# Keyglove_Kit_v0_4.net
KiCad netlist of a schematic drawn in EAGLE
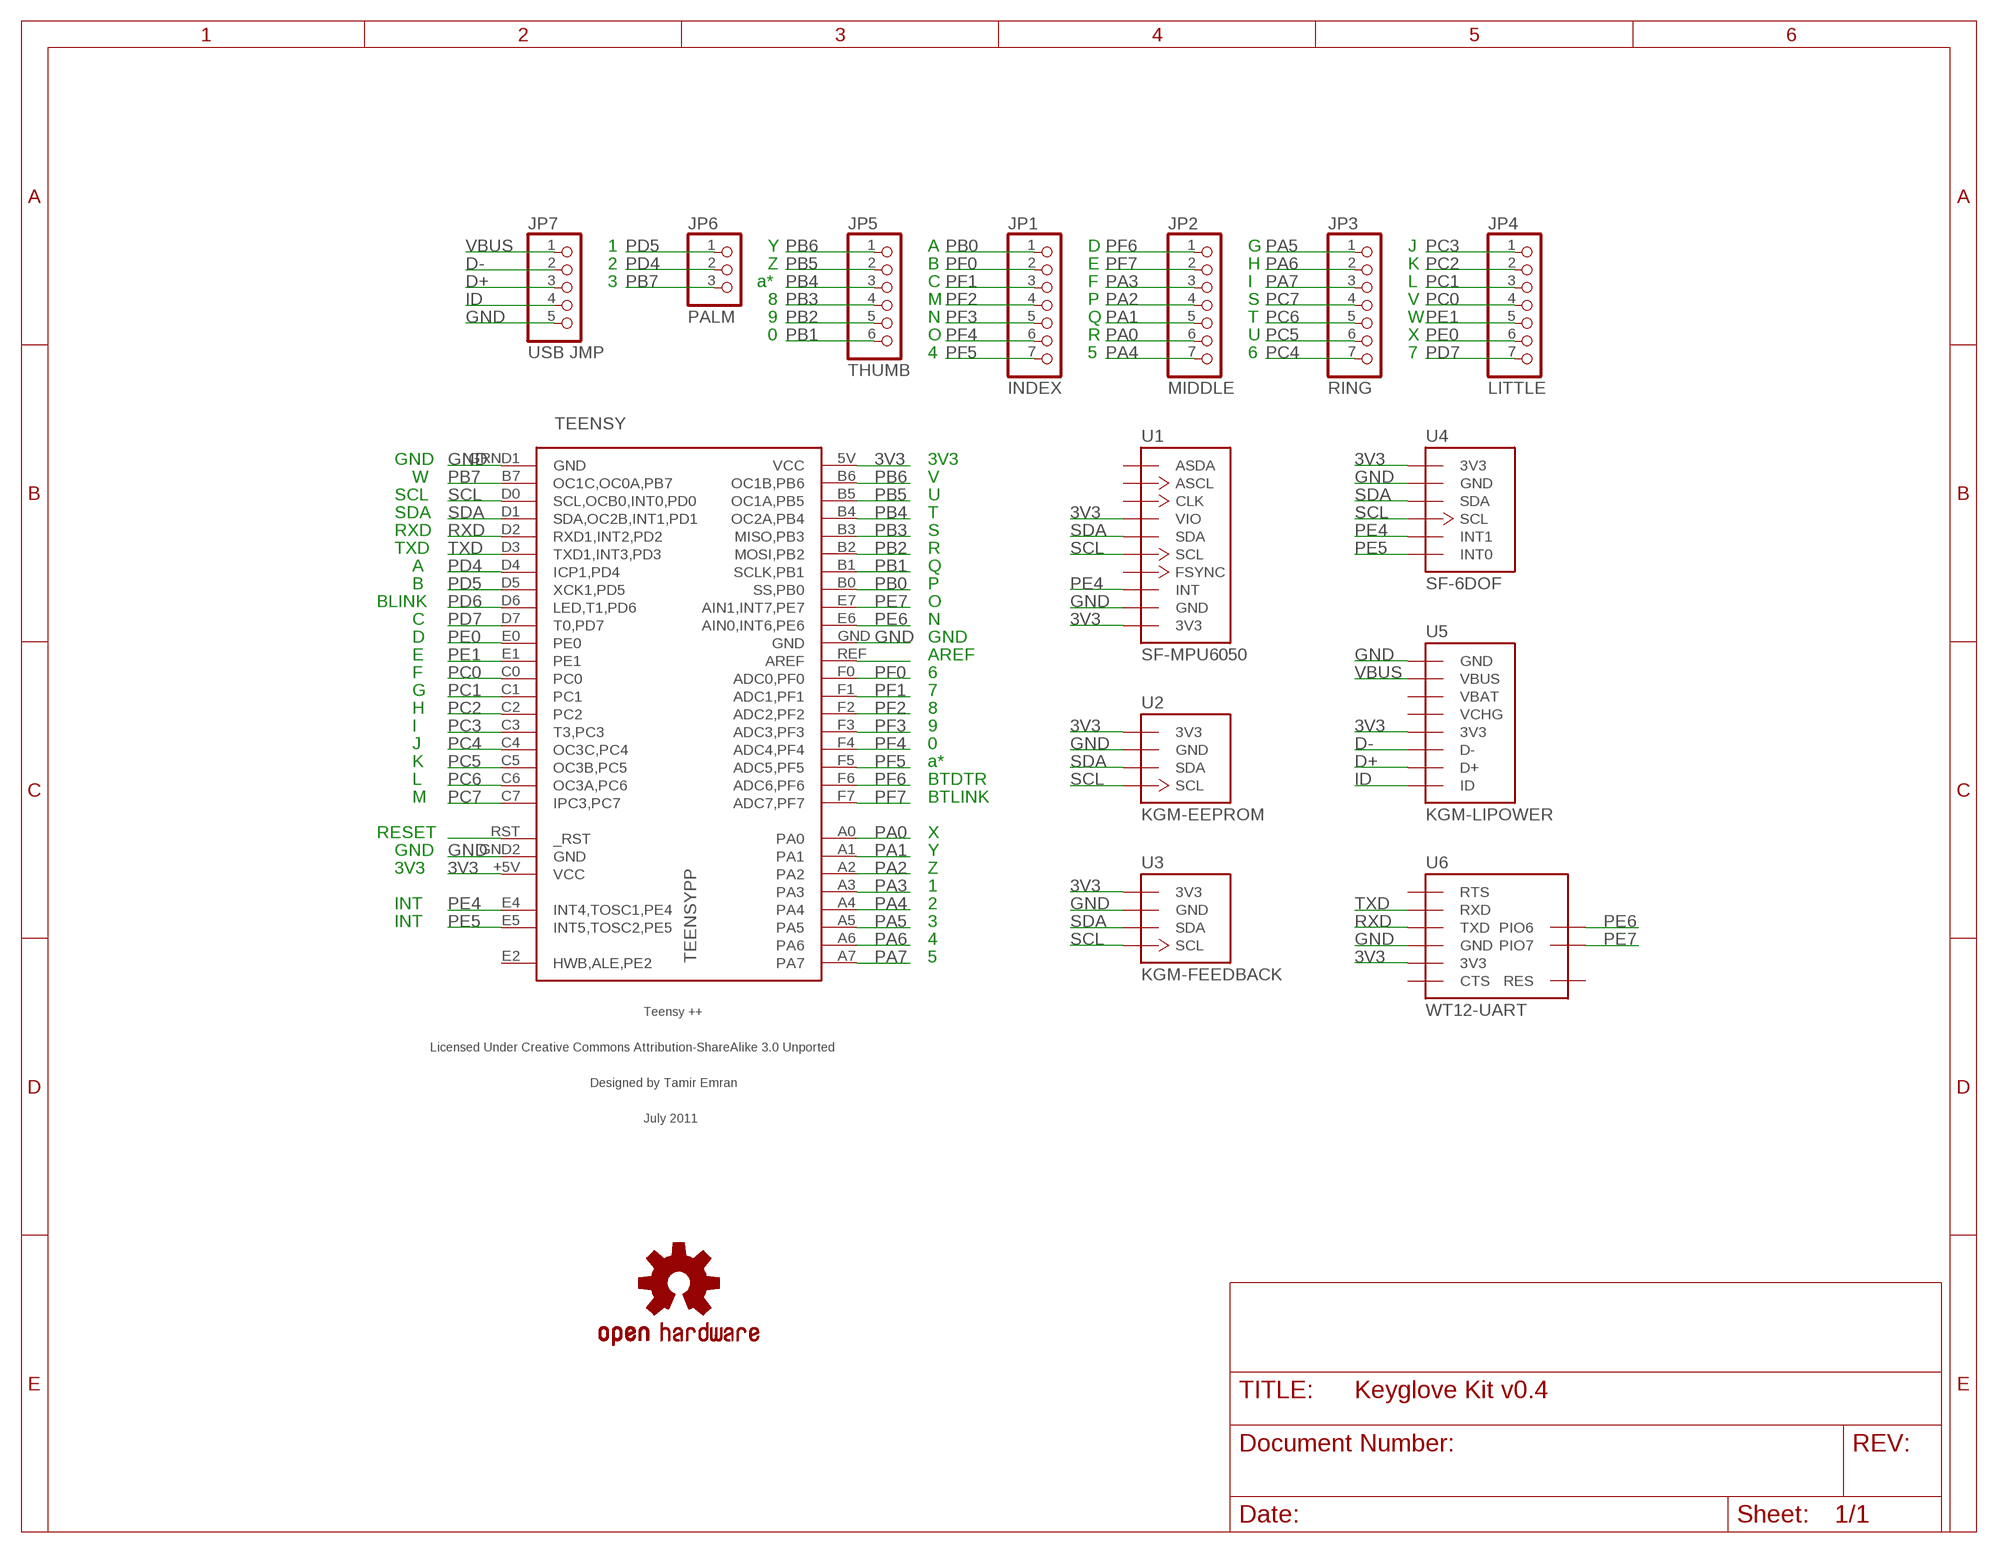
[diagram p0: schematic, sheet 1]

(export (version "E")
  (design (tool "Eeschema 10.0.6"))
  (components
    (comp (ref "JP1")
      (value "INDEX")
      (footprint "eagle-import:1X07")
      (libsource (lib "eagle-import") (part "PINHD-1X7"))
    )
    (comp (ref "JP2")
      (value "MIDDLE")
      (footprint "eagle-import:1X07")
      (libsource (lib "eagle-import") (part "PINHD-1X7"))
    )
    (comp (ref "JP3")
      (value "RING")
      (footprint "eagle-import:1X07")
      (libsource (lib "eagle-import") (part "PINHD-1X7"))
    )
    (comp (ref "JP4")
      (value "LITTLE")
      (footprint "eagle-import:1X07")
      (libsource (lib "eagle-import") (part "PINHD-1X7"))
    )
    (comp (ref "JP5")
      (value "THUMB")
      (footprint "eagle-import:1X06")
      (libsource (lib "eagle-import") (part "PINHD-1X6"))
    )
    (comp (ref "JP6")
      (value "PALM")
      (footprint "eagle-import:1X03")
      (libsource (lib "eagle-import") (part "PINHD-1X3"))
    )
    (comp (ref "JP7")
      (value "USB JMP")
      (footprint "eagle-import:1X05")
      (libsource (lib "eagle-import") (part "PINHD-1X5"))
    )
    (comp (ref "TEENSY")
      (value "TEENSYPP")
      (footprint "eagle-import:TEENSYPP")
      (libsource (lib "eagle-import") (part "TEENSYPP"))
    )
    (comp (ref "U$1")
      (value "OSHW-LOGOM")
      (footprint "eagle-import:OSHW-LOGO-M")
      (libsource (lib "eagle-import") (part "OSHW-LOGOM"))
    )
    (comp (ref "U1")
      (value "SF-MPU6050")
      (footprint "eagle-import:SF-MPU6050")
      (libsource (lib "eagle-import") (part "SF-MPU6050"))
    )
    (comp (ref "U2")
      (value "KGM-EEPROM")
      (footprint "eagle-import:KGM-EEPROM")
      (libsource (lib "eagle-import") (part "KGM-EEPROM"))
    )
    (comp (ref "U3")
      (value "KGM-FEEDBACK")
      (footprint "eagle-import:KGM-FEEDBACK")
      (libsource (lib "eagle-import") (part "KGM-FEEDBACK"))
    )
    (comp (ref "U4")
      (value "SF-6DOF")
      (footprint "eagle-import:SF-6DOF")
      (libsource (lib "eagle-import") (part "SF-6DOF"))
    )
    (comp (ref "U5")
      (value "KGM-LIPOWER")
      (footprint "eagle-import:KGM-LIPOWER")
      (libsource (lib "eagle-import") (part "KGM-LIPOWER"))
    )
    (comp (ref "U6")
      (value "WT12-UART")
      (footprint "eagle-import:WT12-UART")
      (libsource (lib "eagle-import") (part "WT12-UART"))
    )
  )
  (nets
    (net (code "1") (name "/3V3") (class "Default")
      (node (ref "TEENSY") (pin "+5V") (pinfunction "VCC_+5V") (pintype "power_in"))
      (node (ref "TEENSY") (pin "5V") (pinfunction "VCC_5V") (pintype "power_in"))
      (node (ref "U1") (pin "3V3") (pinfunction "3V3_3V3") (pintype "power_in"))
      (node (ref "U1") (pin "VIO") (pinfunction "VIO_VIO") (pintype "power_in"))
      (node (ref "U2") (pin "3V3") (pinfunction "3V3_3V3") (pintype "power_in"))
      (node (ref "U3") (pin "3V3") (pinfunction "3V3_3V3") (pintype "power_in"))
      (node (ref "U4") (pin "3V3") (pinfunction "3V3_3V3") (pintype "power_in"))
      (node (ref "U5") (pin "3V3") (pinfunction "3V3_3V3") (pintype "power_in"))
      (node (ref "U6") (pin "3V3") (pinfunction "3V3_3V3") (pintype "power_in"))
    )
    (net (code "2") (name "/D+") (class "Default")
      (node (ref "JP7") (pin "3") (pinfunction "3_3") (pintype "passive"))
      (node (ref "U5") (pin "D+") (pinfunction "D+_D+") (pintype "bidirectional"))
    )
    (net (code "3") (name "/D-") (class "Default")
      (node (ref "JP7") (pin "2") (pinfunction "2_2") (pintype "passive"))
      (node (ref "U5") (pin "D-") (pinfunction "D-_D-") (pintype "bidirectional"))
    )
    (net (code "4") (name "/GND") (class "Default")
      (node (ref "JP7") (pin "5") (pinfunction "5_5") (pintype "passive"))
      (node (ref "TEENSY") (pin "GND") (pinfunction "GND_GND") (pintype "power_in"))
      (node (ref "TEENSY") (pin "GND2") (pinfunction "GND_GND2") (pintype "power_in"))
      (node (ref "TEENSY") (pin "GRND1") (pinfunction "GND_GRND1") (pintype "power_in"))
      (node (ref "U1") (pin "GND") (pinfunction "GND_GND") (pintype "power_in"))
      (node (ref "U2") (pin "GND") (pinfunction "GND_GND") (pintype "power_in"))
      (node (ref "U3") (pin "GND") (pinfunction "GND_GND") (pintype "power_in"))
      (node (ref "U4") (pin "GND") (pinfunction "GND_GND") (pintype "power_in"))
      (node (ref "U5") (pin "GND") (pinfunction "GND_GND") (pintype "power_in"))
      (node (ref "U6") (pin "GND") (pinfunction "GND_GND") (pintype "power_in"))
    )
    (net (code "5") (name "/ID") (class "Default")
      (node (ref "JP7") (pin "4") (pinfunction "4_4") (pintype "passive"))
      (node (ref "U5") (pin "ID") (pinfunction "ID_ID") (pintype "bidirectional"))
    )
    (net (code "6") (name "/PA0") (class "Default")
      (node (ref "JP2") (pin "6") (pinfunction "6_6") (pintype "passive"))
      (node (ref "TEENSY") (pin "A0") (pinfunction "PA0_A0") (pintype "bidirectional"))
    )
    (net (code "7") (name "/PA1") (class "Default")
      (node (ref "JP2") (pin "5") (pinfunction "5_5") (pintype "passive"))
      (node (ref "TEENSY") (pin "A1") (pinfunction "PA1_A1") (pintype "bidirectional"))
    )
    (net (code "8") (name "/PA2") (class "Default")
      (node (ref "JP2") (pin "4") (pinfunction "4_4") (pintype "passive"))
      (node (ref "TEENSY") (pin "A2") (pinfunction "PA2_A2") (pintype "bidirectional"))
    )
    (net (code "9") (name "/PA3") (class "Default")
      (node (ref "JP2") (pin "3") (pinfunction "3_3") (pintype "passive"))
      (node (ref "TEENSY") (pin "A3") (pinfunction "PA3_A3") (pintype "bidirectional"))
    )
    (net (code "10") (name "/PA4") (class "Default")
      (node (ref "JP2") (pin "7") (pinfunction "7_7") (pintype "passive"))
      (node (ref "TEENSY") (pin "A4") (pinfunction "PA4_A4") (pintype "bidirectional"))
    )
    (net (code "11") (name "/PA5") (class "Default")
      (node (ref "JP3") (pin "1") (pinfunction "1_1") (pintype "passive"))
      (node (ref "TEENSY") (pin "A5") (pinfunction "PA5_A5") (pintype "bidirectional"))
    )
    (net (code "12") (name "/PA6") (class "Default")
      (node (ref "JP3") (pin "2") (pinfunction "2_2") (pintype "passive"))
      (node (ref "TEENSY") (pin "A6") (pinfunction "PA6_A6") (pintype "bidirectional"))
    )
    (net (code "13") (name "/PA7") (class "Default")
      (node (ref "JP3") (pin "3") (pinfunction "3_3") (pintype "passive"))
      (node (ref "TEENSY") (pin "A7") (pinfunction "PA7_A7") (pintype "bidirectional"))
    )
    (net (code "14") (name "/PB0") (class "Default")
      (node (ref "JP1") (pin "1") (pinfunction "1_1") (pintype "passive"))
      (node (ref "TEENSY") (pin "B0") (pinfunction "SS,PB0_B0") (pintype "bidirectional"))
    )
    (net (code "15") (name "/PB1") (class "Default")
      (node (ref "JP5") (pin "6") (pinfunction "6_6") (pintype "passive"))
      (node (ref "TEENSY") (pin "B1") (pinfunction "SCLK,PB1_B1") (pintype "bidirectional"))
    )
    (net (code "16") (name "/PB2") (class "Default")
      (node (ref "JP5") (pin "5") (pinfunction "5_5") (pintype "passive"))
      (node (ref "TEENSY") (pin "B2") (pinfunction "MOSI,PB2_B2") (pintype "bidirectional"))
    )
    (net (code "17") (name "/PB3") (class "Default")
      (node (ref "JP5") (pin "4") (pinfunction "4_4") (pintype "passive"))
      (node (ref "TEENSY") (pin "B3") (pinfunction "MISO,PB3_B3") (pintype "bidirectional"))
    )
    (net (code "18") (name "/PB4") (class "Default")
      (node (ref "JP5") (pin "3") (pinfunction "3_3") (pintype "passive"))
      (node (ref "TEENSY") (pin "B4") (pinfunction "OC2A,PB4_B4") (pintype "bidirectional"))
    )
    (net (code "19") (name "/PB5") (class "Default")
      (node (ref "JP5") (pin "2") (pinfunction "2_2") (pintype "passive"))
      (node (ref "TEENSY") (pin "B5") (pinfunction "OC1A,PB5_B5") (pintype "bidirectional"))
    )
    (net (code "20") (name "/PB6") (class "Default")
      (node (ref "JP5") (pin "1") (pinfunction "1_1") (pintype "passive"))
      (node (ref "TEENSY") (pin "B6") (pinfunction "OC1B,PB6_B6") (pintype "bidirectional"))
    )
    (net (code "21") (name "/PB7") (class "Default")
      (node (ref "JP6") (pin "3") (pinfunction "3_3") (pintype "passive"))
      (node (ref "TEENSY") (pin "B7") (pinfunction "OC1C,OC0A,PB7_B7") (pintype "bidirectional"))
    )
    (net (code "22") (name "/PC0") (class "Default")
      (node (ref "JP4") (pin "4") (pinfunction "4_4") (pintype "passive"))
      (node (ref "TEENSY") (pin "C0") (pinfunction "PC0_C0") (pintype "bidirectional"))
    )
    (net (code "23") (name "/PC1") (class "Default")
      (node (ref "JP4") (pin "3") (pinfunction "3_3") (pintype "passive"))
      (node (ref "TEENSY") (pin "C1") (pinfunction "PC1_C1") (pintype "bidirectional"))
    )
    (net (code "24") (name "/PC2") (class "Default")
      (node (ref "JP4") (pin "2") (pinfunction "2_2") (pintype "passive"))
      (node (ref "TEENSY") (pin "C2") (pinfunction "PC2_C2") (pintype "bidirectional"))
    )
    (net (code "25") (name "/PC3") (class "Default")
      (node (ref "JP4") (pin "1") (pinfunction "1_1") (pintype "passive"))
      (node (ref "TEENSY") (pin "C3") (pinfunction "T3,PC3_C3") (pintype "bidirectional"))
    )
    (net (code "26") (name "/PC4") (class "Default")
      (node (ref "JP3") (pin "7") (pinfunction "7_7") (pintype "passive"))
      (node (ref "TEENSY") (pin "C4") (pinfunction "OC3C,PC4_C4") (pintype "bidirectional"))
    )
    (net (code "27") (name "/PC5") (class "Default")
      (node (ref "JP3") (pin "6") (pinfunction "6_6") (pintype "passive"))
      (node (ref "TEENSY") (pin "C5") (pinfunction "OC3B,PC5_C5") (pintype "bidirectional"))
    )
    (net (code "28") (name "/PC6") (class "Default")
      (node (ref "JP3") (pin "5") (pinfunction "5_5") (pintype "passive"))
      (node (ref "TEENSY") (pin "C6") (pinfunction "OC3A,PC6_C6") (pintype "bidirectional"))
    )
    (net (code "29") (name "/PC7") (class "Default")
      (node (ref "JP3") (pin "4") (pinfunction "4_4") (pintype "passive"))
      (node (ref "TEENSY") (pin "C7") (pinfunction "IPC3,PC7_C7") (pintype "bidirectional"))
    )
    (net (code "30") (name "/PD4") (class "Default")
      (node (ref "JP6") (pin "2") (pinfunction "2_2") (pintype "passive"))
      (node (ref "TEENSY") (pin "D4") (pinfunction "ICP1,PD4_D4") (pintype "bidirectional"))
    )
    (net (code "31") (name "/PD5") (class "Default")
      (node (ref "JP6") (pin "1") (pinfunction "1_1") (pintype "passive"))
      (node (ref "TEENSY") (pin "D5") (pinfunction "XCK1,PD5_D5") (pintype "bidirectional"))
    )
    (net (code "32") (name "/PD6") (class "Default")
      (node (ref "TEENSY") (pin "D6") (pinfunction "LED,T1,PD6_D6") (pintype "bidirectional"))
    )
    (net (code "33") (name "/PD7") (class "Default")
      (node (ref "JP4") (pin "7") (pinfunction "7_7") (pintype "passive"))
      (node (ref "TEENSY") (pin "D7") (pinfunction "T0,PD7_D7") (pintype "bidirectional"))
    )
    (net (code "34") (name "/PE0") (class "Default")
      (node (ref "JP4") (pin "6") (pinfunction "6_6") (pintype "passive"))
      (node (ref "TEENSY") (pin "E0") (pinfunction "PE0_E0") (pintype "bidirectional"))
    )
    (net (code "35") (name "/PE1") (class "Default")
      (node (ref "JP4") (pin "5") (pinfunction "5_5") (pintype "passive"))
      (node (ref "TEENSY") (pin "E1") (pinfunction "PE1_E1") (pintype "bidirectional"))
    )
    (net (code "36") (name "/PE4") (class "Default")
      (node (ref "TEENSY") (pin "E4") (pinfunction "INT4,TOSC1,PE4_E4") (pintype "bidirectional"))
      (node (ref "U1") (pin "INT") (pinfunction "INT_INT") (pintype "output"))
      (node (ref "U4") (pin "INT1") (pinfunction "INT1_INT1") (pintype "output"))
    )
    (net (code "37") (name "/PE5") (class "Default")
      (node (ref "TEENSY") (pin "E5") (pinfunction "INT5,TOSC2,PE5_E5") (pintype "bidirectional"))
      (node (ref "U4") (pin "INT0") (pinfunction "INT0_INT0") (pintype "output"))
    )
    (net (code "38") (name "/PE6") (class "Default")
      (node (ref "TEENSY") (pin "E6") (pinfunction "AIN0,INT6,PE6_E6") (pintype "bidirectional"))
      (node (ref "U6") (pin "PIO6") (pinfunction "PIO6_PIO6") (pintype "bidirectional"))
    )
    (net (code "39") (name "/PE7") (class "Default")
      (node (ref "TEENSY") (pin "E7") (pinfunction "AIN1,INT7,PE7_E7") (pintype "bidirectional"))
      (node (ref "U6") (pin "PIO7") (pinfunction "PIO7_PIO7") (pintype "bidirectional"))
    )
    (net (code "40") (name "/PF0") (class "Default")
      (node (ref "JP1") (pin "2") (pinfunction "2_2") (pintype "passive"))
      (node (ref "TEENSY") (pin "F0") (pinfunction "ADC0,PF0_F0") (pintype "bidirectional"))
    )
    (net (code "41") (name "/PF1") (class "Default")
      (node (ref "JP1") (pin "3") (pinfunction "3_3") (pintype "passive"))
      (node (ref "TEENSY") (pin "F1") (pinfunction "ADC1,PF1_F1") (pintype "bidirectional"))
    )
    (net (code "42") (name "/PF2") (class "Default")
      (node (ref "JP1") (pin "4") (pinfunction "4_4") (pintype "passive"))
      (node (ref "TEENSY") (pin "F2") (pinfunction "ADC2,PF2_F2") (pintype "bidirectional"))
    )
    (net (code "43") (name "/PF3") (class "Default")
      (node (ref "JP1") (pin "5") (pinfunction "5_5") (pintype "passive"))
      (node (ref "TEENSY") (pin "F3") (pinfunction "ADC3,PF3_F3") (pintype "bidirectional"))
    )
    (net (code "44") (name "/PF4") (class "Default")
      (node (ref "JP1") (pin "6") (pinfunction "6_6") (pintype "passive"))
      (node (ref "TEENSY") (pin "F4") (pinfunction "ADC4,PF4_F4") (pintype "bidirectional"))
    )
    (net (code "45") (name "/PF5") (class "Default")
      (node (ref "JP1") (pin "7") (pinfunction "7_7") (pintype "passive"))
      (node (ref "TEENSY") (pin "F5") (pinfunction "ADC5,PF5_F5") (pintype "bidirectional"))
    )
    (net (code "46") (name "/PF6") (class "Default")
      (node (ref "JP2") (pin "1") (pinfunction "1_1") (pintype "passive"))
      (node (ref "TEENSY") (pin "F6") (pinfunction "ADC6,PF6_F6") (pintype "bidirectional"))
    )
    (net (code "47") (name "/PF7") (class "Default")
      (node (ref "JP2") (pin "2") (pinfunction "2_2") (pintype "passive"))
      (node (ref "TEENSY") (pin "F7") (pinfunction "ADC7,PF7_F7") (pintype "bidirectional"))
    )
    (net (code "48") (name "/RXD") (class "Default")
      (node (ref "TEENSY") (pin "D2") (pinfunction "RXD1,INT2,PD2_D2") (pintype "bidirectional"))
      (node (ref "U6") (pin "TXD") (pinfunction "TXD_TXD") (pintype "output"))
    )
    (net (code "49") (name "/SCL") (class "Default")
      (node (ref "TEENSY") (pin "D0") (pinfunction "SCL,OCB0,INT0,PD0_D0") (pintype "bidirectional"))
      (node (ref "U1") (pin "SCL") (pinfunction "SCL_SCL") (pintype "bidirectional"))
      (node (ref "U2") (pin "SCL") (pinfunction "SCL_SCL") (pintype "bidirectional"))
      (node (ref "U3") (pin "SCL") (pinfunction "SCL_SCL") (pintype "bidirectional"))
      (node (ref "U4") (pin "SCL") (pinfunction "SCL_SCL") (pintype "bidirectional"))
    )
    (net (code "50") (name "/SDA") (class "Default")
      (node (ref "TEENSY") (pin "D1") (pinfunction "SDA,OC2B,INT1,PD1_D1") (pintype "bidirectional"))
      (node (ref "U1") (pin "SDA") (pinfunction "SDA_SDA") (pintype "bidirectional"))
      (node (ref "U2") (pin "SDA") (pinfunction "SDA_SDA") (pintype "bidirectional"))
      (node (ref "U3") (pin "SDA") (pinfunction "SDA_SDA") (pintype "bidirectional"))
      (node (ref "U4") (pin "SDA") (pinfunction "SDA_SDA") (pintype "bidirectional"))
    )
    (net (code "51") (name "/TXD") (class "Default")
      (node (ref "TEENSY") (pin "D3") (pinfunction "TXD1,INT3,PD3_D3") (pintype "bidirectional"))
      (node (ref "U6") (pin "RXD") (pinfunction "RXD_RXD") (pintype "input"))
    )
    (net (code "52") (name "/VBAT") (class "Default")
      (node (ref "U5") (pin "VBAT") (pinfunction "VBAT_VBAT") (pintype "power_in"))
    )
    (net (code "53") (name "/VBUS") (class "Default")
      (node (ref "JP7") (pin "1") (pinfunction "1_1") (pintype "passive"))
      (node (ref "U5") (pin "VBUS") (pinfunction "VBUS_VBUS") (pintype "power_in"))
    )
    (net (code "54") (name "/VCHG") (class "Default")
      (node (ref "U5") (pin "VCHG") (pinfunction "VCHG_VCHG") (pintype "power_in"))
    )
    (net (code "55") (name "unconnected-(TEENSY-AREF-PadREF)") (class "Default")
      (node (ref "TEENSY") (pin "REF") (pinfunction "AREF_REF") (pintype "input"))
    )
    (net (code "56") (name "unconnected-(TEENSY-HWB,ALE,PE2-PadE2)") (class "Default")
      (node (ref "TEENSY") (pin "E2") (pinfunction "HWB,ALE,PE2_E2") (pintype "bidirectional"))
    )
    (net (code "57") (name "unconnected-(TEENSY-_RST-PadRST)") (class "Default")
      (node (ref "TEENSY") (pin "RST") (pinfunction "_RST_RST") (pintype "input"))
    )
    (net (code "58") (name "unconnected-(U1-PadASCL)") (class "Default")
      (node (ref "U1") (pin "ASCL") (pinfunction "ASCL_ASCL") (pintype "bidirectional"))
    )
    (net (code "59") (name "unconnected-(U1-PadASDA)") (class "Default")
      (node (ref "U1") (pin "ASDA") (pinfunction "ASDA_ASDA") (pintype "bidirectional"))
    )
    (net (code "60") (name "unconnected-(U1-PadCLK)") (class "Default")
      (node (ref "U1") (pin "CLK") (pinfunction "CLK_CLK") (pintype "bidirectional"))
    )
    (net (code "61") (name "unconnected-(U1-PadFSYNC)") (class "Default")
      (node (ref "U1") (pin "FSYNC") (pinfunction "FSYNC_FSYNC") (pintype "bidirectional"))
    )
    (net (code "62") (name "unconnected-(U6-PadCTS)") (class "Default")
      (node (ref "U6") (pin "CTS") (pinfunction "CTS_CTS") (pintype "input"))
    )
    (net (code "63") (name "unconnected-(U6-PadRTS)") (class "Default")
      (node (ref "U6") (pin "RTS") (pinfunction "RTS_RTS") (pintype "output"))
    )
    (net (code "64") (name "unconnected-(U6-RES-PadRESET)") (class "Default")
      (node (ref "U6") (pin "RESET") (pinfunction "RES_RESET") (pintype "input"))
    )
  )
)
